# EEpromConfig.net
KiCad netlist of a schematic drawn in Altium Designer
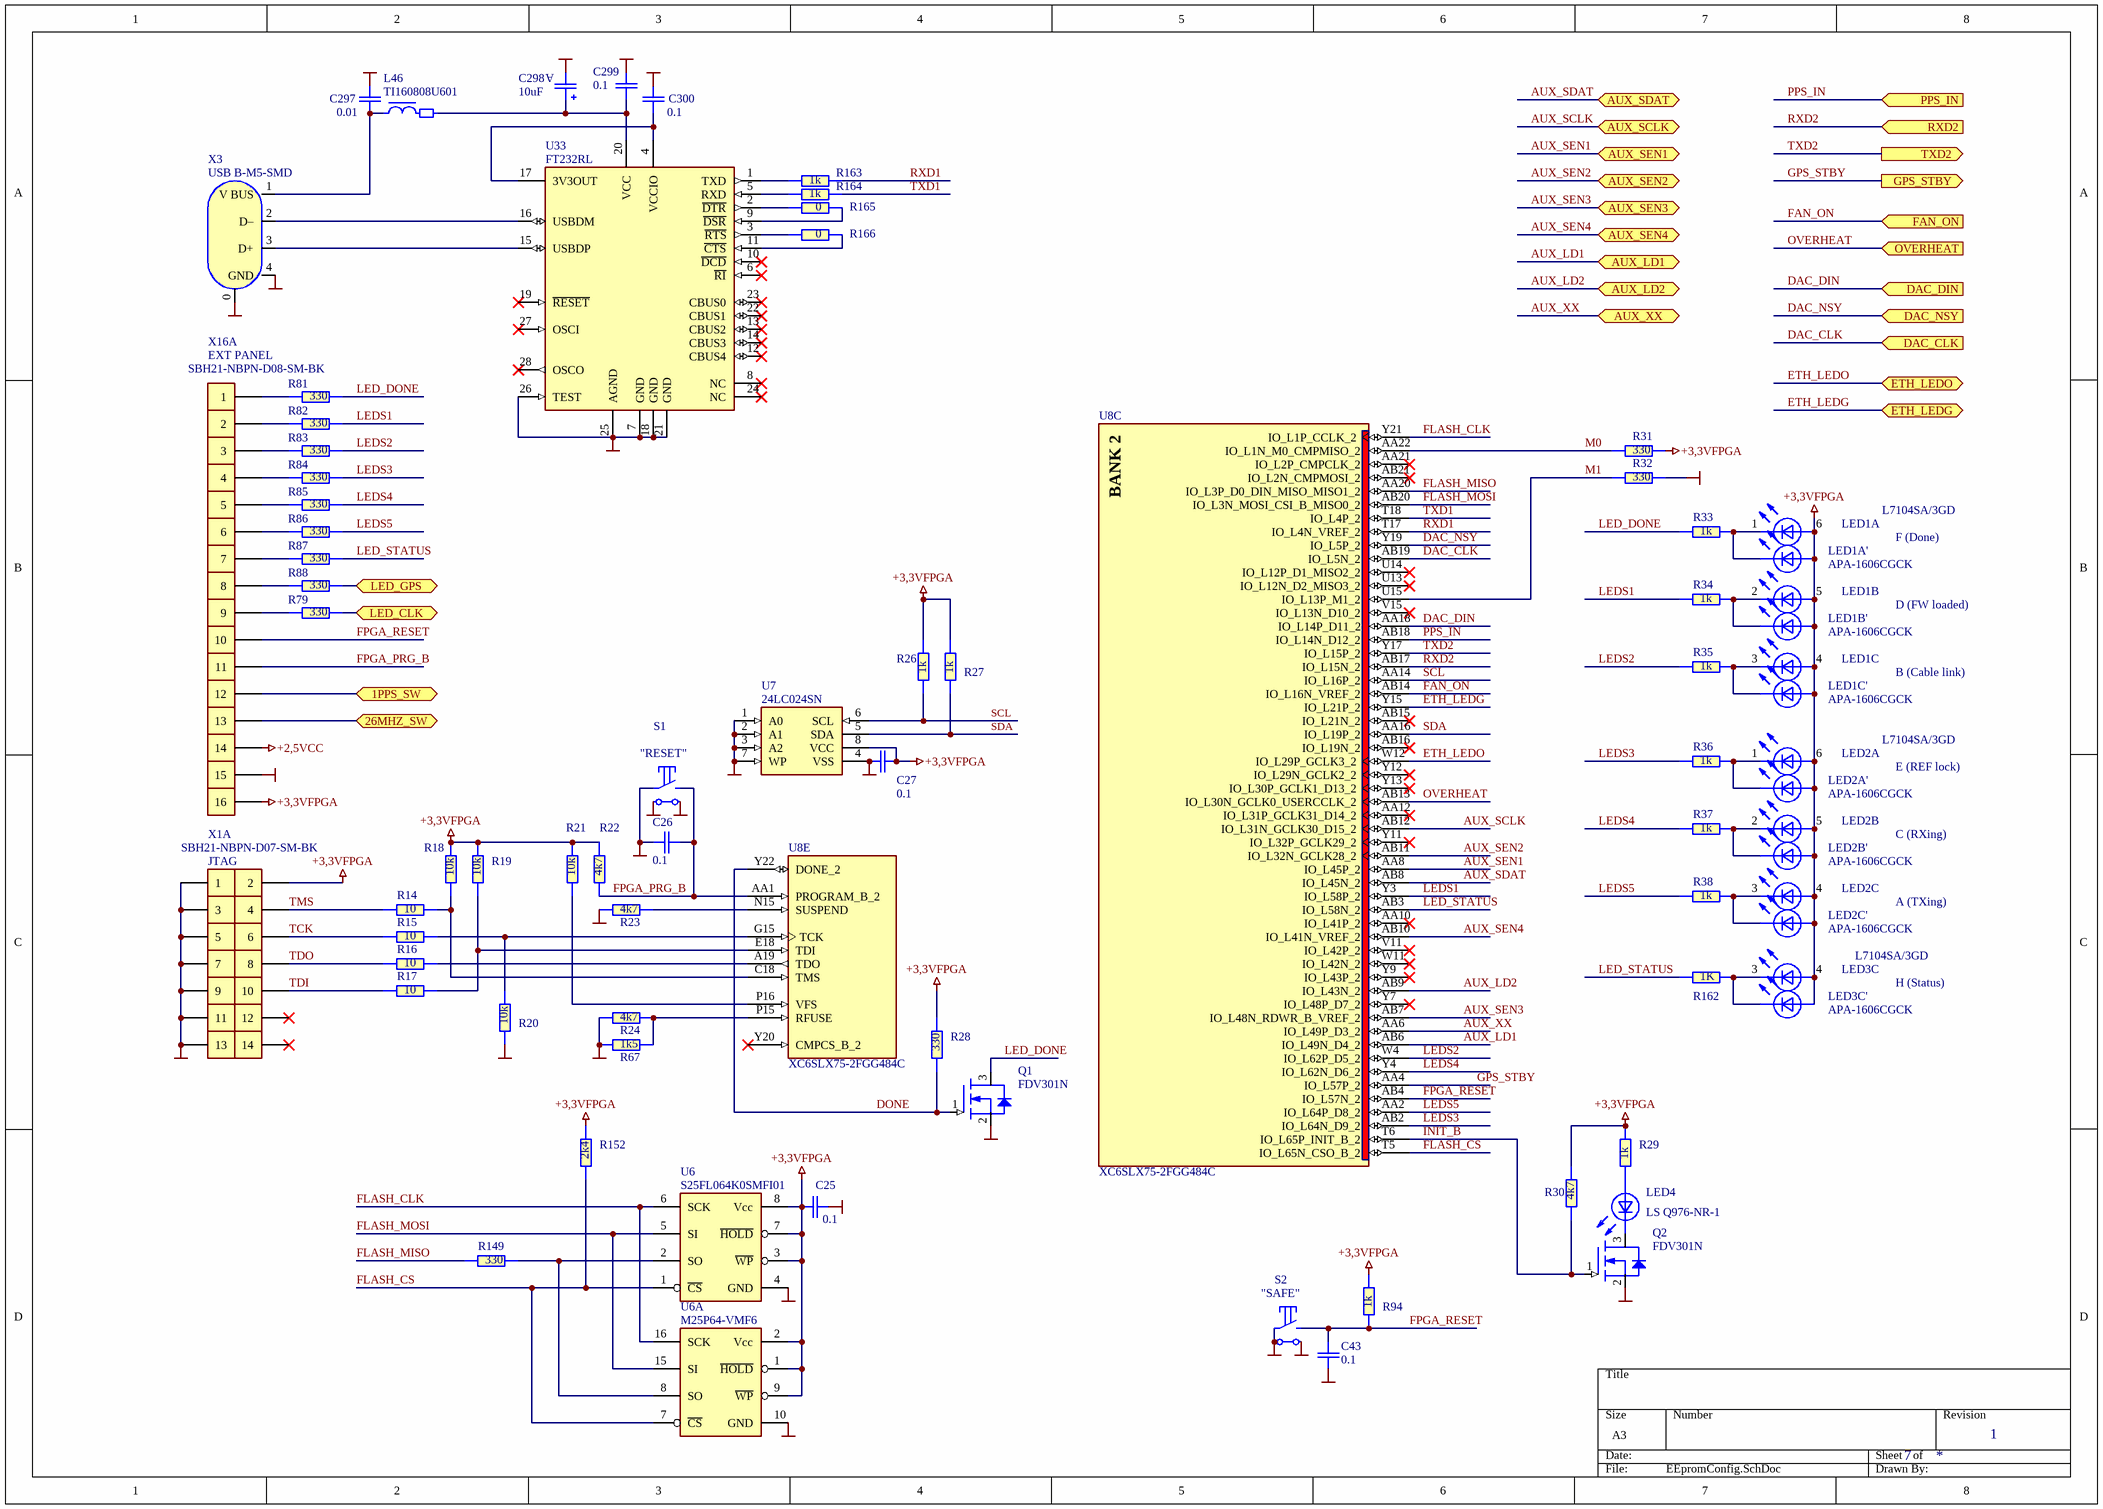
[diagram p0: EEpromConfig.SchDoc]

(export (version "E")
  (design (tool "Eeschema 10.0.6"))
  (components
    (comp (ref "C25")
      (value "0.1")
      (footprint "C0402-Phillips")
      (description "Конденсатор")
      (fields (field (name "MANUFACTURER") "MURATA") (field (name "TOLERANCE") "20%"))
      (libsource (lib "Capacitors") (part "C0402"))
    )
    (comp (ref "C26")
      (value "0.1")
      (footprint "C0402-Phillips")
      (description "Конденсатор")
      (fields (field (name "MANUFACTURER") "MURATA") (field (name "TOLERANCE") "20%"))
      (libsource (lib "Capacitors") (part "C0402"))
    )
    (comp (ref "C27")
      (value "0.1")
      (footprint "C0402-Phillips")
      (description "Конденсатор")
      (fields (field (name "MANUFACTURER") "MURATA") (field (name "TOLERANCE") "20%"))
      (libsource (lib "Capacitors") (part "C0402"))
    )
    (comp (ref "C43")
      (value "0.1")
      (footprint "C0402-Phillips")
      (description "Конденсатор")
      (fields (field (name "MANUFACTURER") "MURATA") (field (name "TOLERANCE") "20%"))
      (libsource (lib "Capacitors") (part "C0402"))
    )
    (comp (ref "C297")
      (value "0.01")
      (footprint "C0603-PHILLIPS")
      (description "Конденсатор")
      (fields (field (name "MANUFACTURER") "MURATA") (field (name "TOLERANCE") "20%"))
      (libsource (lib "Capacitors") (part "C0603"))
    )
    (comp (ref "C298")
      (value "10uF")
      (footprint "CA3216")
      (description "Конденсатор")
      (fields (field (name "MANUFACTURER") "SPRAGUE"))
      (libsource (lib "Capacitors") (part "CA3216"))
    )
    (comp (ref "C299")
      (value "0.1")
      (footprint "C0603-PHILLIPS")
      (description "Конденсатор")
      (fields (field (name "MANUFACTURER") "MURATA") (field (name "TOLERANCE") "20%"))
      (libsource (lib "Capacitors") (part "C0603"))
    )
    (comp (ref "C300")
      (value "0.1")
      (footprint "C0603-PHILLIPS")
      (description "Конденсатор")
      (fields (field (name "MANUFACTURER") "MURATA") (field (name "TOLERANCE") "20%"))
      (libsource (lib "Capacitors") (part "C0603"))
    )
    (comp (ref "L46")
      (value "TI160808U601")
      (footprint "Ti160808-Phillips")
      (description "Дроссель ЭМС")
      (fields (field (name "MANUFACTURER") "MURATA"))
      (libsource (lib "altium-import") (part "root_0_TI160808_"))
    )
    (comp (ref "LED1")
      (value "L7104SA/3GD")
      (footprint "L-7104SA/3")
      (description "Светодиод")
      (fields (field (name "MANUFACTURER") "KINGBRIGTH"))
      (libsource (lib "Diods") (part "L7104SA/3"))
    )
    (comp (ref "LED1A'")
      (value "APA-1606CGCK")
      (footprint "KPA-1606g")
      (description "Светодиод")
      (fields (field (name "MANUFACTURER") "Kingbright"))
      (libsource (lib "Diods") (part "KPA-1606"))
    )
    (comp (ref "LED1B'")
      (value "APA-1606CGCK")
      (footprint "KPA-1606g")
      (description "Светодиод")
      (fields (field (name "MANUFACTURER") "Kingbright"))
      (libsource (lib "Diods") (part "KPA-1606"))
    )
    (comp (ref "LED1C'")
      (value "APA-1606CGCK")
      (footprint "KPA-1606g")
      (description "Светодиод")
      (fields (field (name "MANUFACTURER") "Kingbright"))
      (libsource (lib "Diods") (part "KPA-1606"))
    )
    (comp (ref "LED2")
      (value "L7104SA/3GD")
      (footprint "L-7104SA/3")
      (description "Светодиод")
      (fields (field (name "MANUFACTURER") "KINGBRIGTH"))
      (libsource (lib "Diods") (part "L7104SA/3"))
    )
    (comp (ref "LED2A'")
      (value "APA-1606CGCK")
      (footprint "KPA-1606g")
      (description "Светодиод")
      (fields (field (name "MANUFACTURER") "Kingbright"))
      (libsource (lib "Diods") (part "KPA-1606"))
    )
    (comp (ref "LED2B'")
      (value "APA-1606CGCK")
      (footprint "KPA-1606g")
      (description "Светодиод")
      (fields (field (name "MANUFACTURER") "Kingbright"))
      (libsource (lib "Diods") (part "KPA-1606"))
    )
    (comp (ref "LED2C'")
      (value "APA-1606CGCK")
      (footprint "KPA-1606g")
      (description "Светодиод")
      (fields (field (name "MANUFACTURER") "Kingbright"))
      (libsource (lib "Diods") (part "KPA-1606"))
    )
    (comp (ref "LED3")
      (value "L7104SA/3GD")
      (footprint "L-7104SA/3")
      (description "Светодиод")
      (fields (field (name "MANUFACTURER") "KINGBRIGTH"))
      (libsource (lib "Diods") (part "L7104SA/3"))
    )
    (comp (ref "LED3C'")
      (value "APA-1606CGCK")
      (footprint "KPA-1606g")
      (description "Светодиод")
      (fields (field (name "MANUFACTURER") "Kingbright"))
      (libsource (lib "Diods") (part "KPA-1606"))
    )
    (comp (ref "LED4")
      (value "LS Q976-NR-1")
      (footprint "LED-0603y")
      (description "LED SMD")
      (fields (field (name "MANUFACTURER") "OSRAM Opto Semiconductors Inc"))
      (libsource (lib "altium-import") (part "root_2_LED0603_"))
    )
    (comp (ref "Q1")
      (value "FDV301N")
      (footprint "SOT23-Philips")
      (description "Транзистор")
      (fields (field (name "MANUFACTURER") "Fairchild"))
      (libsource (lib "Transistors") (part "FDV301N"))
    )
    (comp (ref "Q2")
      (value "FDV301N")
      (footprint "SOT23-Philips")
      (description "Транзистор")
      (fields (field (name "MANUFACTURER") "Fairchild"))
      (libsource (lib "Transistors") (part "FDV301N"))
    )
    (comp (ref "R14")
      (value "10")
      (footprint "R0603-PHILLIPS")
      (description "Резистор")
      (fields (field (name "MANUFACTURER") "YAGEO") (field (name "TOLERANCE") "5%"))
      (libsource (lib "altium-import") (part "root_1_R0603_"))
    )
    (comp (ref "R15")
      (value "10")
      (footprint "R0603-PHILLIPS")
      (description "Резистор")
      (fields (field (name "MANUFACTURER") "YAGEO") (field (name "TOLERANCE") "5%"))
      (libsource (lib "altium-import") (part "root_1_R0603_"))
    )
    (comp (ref "R16")
      (value "10")
      (footprint "R0603-PHILLIPS")
      (description "Резистор")
      (fields (field (name "MANUFACTURER") "YAGEO") (field (name "TOLERANCE") "5%"))
      (libsource (lib "altium-import") (part "root_1_R0603_"))
    )
    (comp (ref "R17")
      (value "10")
      (footprint "R0603-PHILLIPS")
      (description "Резистор")
      (fields (field (name "MANUFACTURER") "YAGEO") (field (name "TOLERANCE") "5%"))
      (libsource (lib "altium-import") (part "root_1_R0603_"))
    )
    (comp (ref "R18")
      (value "10k")
      (footprint "R0603-PHILLIPS")
      (description "Резистор")
      (fields (field (name "MANUFACTURER") "YAGEO") (field (name "TOLERANCE") "5%"))
      (libsource (lib "altium-import") (part "root_0_R0603_"))
    )
    (comp (ref "R19")
      (value "10k")
      (footprint "R0603-PHILLIPS")
      (description "Резистор")
      (fields (field (name "MANUFACTURER") "YAGEO") (field (name "TOLERANCE") "5%"))
      (libsource (lib "altium-import") (part "root_0_R0603_"))
    )
    (comp (ref "R20")
      (value "10k")
      (footprint "R0603-PHILLIPS")
      (description "Резистор")
      (fields (field (name "MANUFACTURER") "YAGEO") (field (name "TOLERANCE") "5%"))
      (libsource (lib "altium-import") (part "root_0_R0603_"))
    )
    (comp (ref "R21")
      (value "10k")
      (footprint "R0603-PHILLIPS")
      (description "Резистор")
      (fields (field (name "MANUFACTURER") "YAGEO") (field (name "TOLERANCE") "5%"))
      (libsource (lib "altium-import") (part "root_0_R0603_"))
    )
    (comp (ref "R22")
      (value "4k7")
      (footprint "R0603-PHILLIPS")
      (description "Резистор")
      (fields (field (name "MANUFACTURER") "YAGEO") (field (name "TOLERANCE") "5%"))
      (libsource (lib "altium-import") (part "root_0_R0603_"))
    )
    (comp (ref "R23")
      (value "4k7")
      (footprint "R0603-PHILLIPS")
      (description "Резистор")
      (fields (field (name "MANUFACTURER") "YAGEO") (field (name "TOLERANCE") "5%"))
      (libsource (lib "altium-import") (part "root_1_R0603_"))
    )
    (comp (ref "R24")
      (value "4k7")
      (footprint "R0603-PHILLIPS")
      (description "Резистор")
      (fields (field (name "MANUFACTURER") "YAGEO") (field (name "TOLERANCE") "5%"))
      (libsource (lib "altium-import") (part "root_1_R0603_"))
    )
    (comp (ref "R26")
      (value "1k")
      (footprint "R0603-PHILLIPS")
      (description "Резистор")
      (fields (field (name "MANUFACTURER") "YAGEO") (field (name "TOLERANCE") "5%"))
      (libsource (lib "altium-import") (part "root_0_R0603_"))
    )
    (comp (ref "R27")
      (value "1k")
      (footprint "R0603-PHILLIPS")
      (description "Резистор")
      (fields (field (name "MANUFACTURER") "YAGEO") (field (name "TOLERANCE") "5%"))
      (libsource (lib "altium-import") (part "root_0_R0603_"))
    )
    (comp (ref "R28")
      (value "330")
      (footprint "R0603-PHILLIPS")
      (description "Резистор")
      (fields (field (name "MANUFACTURER") "YAGEO") (field (name "TOLERANCE") "5%"))
      (libsource (lib "altium-import") (part "root_0_R0603_"))
    )
    (comp (ref "R29")
      (value "1k")
      (footprint "R0603-PHILLIPS")
      (description "Резистор")
      (fields (field (name "MANUFACTURER") "YAGEO") (field (name "TOLERANCE") "5%"))
      (libsource (lib "altium-import") (part "root_0_R0603_"))
    )
    (comp (ref "R30")
      (value "4k7")
      (footprint "R0603-PHILLIPS")
      (description "Резистор")
      (fields (field (name "MANUFACTURER") "YAGEO") (field (name "TOLERANCE") "5%"))
      (libsource (lib "altium-import") (part "root_0_R0603_"))
    )
    (comp (ref "R31")
      (value "330")
      (footprint "R0603-PHILLIPS")
      (description "Резистор")
      (fields (field (name "MANUFACTURER") "YAGEO") (field (name "TOLERANCE") "5%"))
      (libsource (lib "altium-import") (part "root_1_R0603_"))
    )
    (comp (ref "R32")
      (value "330")
      (footprint "R0603-PHILLIPS")
      (description "Резистор")
      (fields (field (name "MANUFACTURER") "YAGEO") (field (name "TOLERANCE") "5%"))
      (libsource (lib "altium-import") (part "root_1_R0603_"))
    )
    (comp (ref "R33")
      (value "1k")
      (footprint "R0603-PHILLIPS")
      (description "Резистор")
      (fields (field (name "MANUFACTURER") "YAGEO") (field (name "TOLERANCE") "5%"))
      (libsource (lib "altium-import") (part "root_3_R0603_"))
    )
    (comp (ref "R34")
      (value "1k")
      (footprint "R0603-PHILLIPS")
      (description "Резистор")
      (fields (field (name "MANUFACTURER") "YAGEO") (field (name "TOLERANCE") "5%"))
      (libsource (lib "altium-import") (part "root_3_R0603_"))
    )
    (comp (ref "R35")
      (value "1k")
      (footprint "R0603-PHILLIPS")
      (description "Резистор")
      (fields (field (name "MANUFACTURER") "YAGEO") (field (name "TOLERANCE") "5%"))
      (libsource (lib "altium-import") (part "root_3_R0603_"))
    )
    (comp (ref "R36")
      (value "1k")
      (footprint "R0603-PHILLIPS")
      (description "Резистор")
      (fields (field (name "MANUFACTURER") "YAGEO") (field (name "TOLERANCE") "5%"))
      (libsource (lib "altium-import") (part "root_3_R0603_"))
    )
    (comp (ref "R37")
      (value "1k")
      (footprint "R0603-PHILLIPS")
      (description "Резистор")
      (fields (field (name "MANUFACTURER") "YAGEO") (field (name "TOLERANCE") "5%"))
      (libsource (lib "altium-import") (part "root_3_R0603_"))
    )
    (comp (ref "R38")
      (value "1k")
      (footprint "R0603-PHILLIPS")
      (description "Резистор")
      (fields (field (name "MANUFACTURER") "YAGEO") (field (name "TOLERANCE") "5%"))
      (libsource (lib "altium-import") (part "root_3_R0603_"))
    )
    (comp (ref "R67")
      (value "1k5")
      (footprint "R0603-PHILLIPS")
      (description "Резистор")
      (fields (field (name "MANUFACTURER") "YAGEO") (field (name "TOLERANCE") "5%"))
      (libsource (lib "altium-import") (part "root_1_R0603_"))
    )
    (comp (ref "R79")
      (value "330")
      (footprint "R0603-PHILLIPS")
      (description "Резистор")
      (fields (field (name "MANUFACTURER") "YAGEO") (field (name "TOLERANCE") "5%"))
      (libsource (lib "altium-import") (part "root_3_mirrored_R0603_"))
    )
    (comp (ref "R81")
      (value "330")
      (footprint "R0603-PHILLIPS")
      (description "Резистор")
      (fields (field (name "MANUFACTURER") "YAGEO") (field (name "TOLERANCE") "5%"))
      (libsource (lib "altium-import") (part "root_3_mirrored_R0603_"))
    )
    (comp (ref "R82")
      (value "330")
      (footprint "R0603-PHILLIPS")
      (description "Резистор")
      (fields (field (name "MANUFACTURER") "YAGEO") (field (name "TOLERANCE") "5%"))
      (libsource (lib "altium-import") (part "root_3_mirrored_R0603_"))
    )
    (comp (ref "R83")
      (value "330")
      (footprint "R0603-PHILLIPS")
      (description "Резистор")
      (fields (field (name "MANUFACTURER") "YAGEO") (field (name "TOLERANCE") "5%"))
      (libsource (lib "altium-import") (part "root_3_mirrored_R0603_"))
    )
    (comp (ref "R84")
      (value "330")
      (footprint "R0603-PHILLIPS")
      (description "Резистор")
      (fields (field (name "MANUFACTURER") "YAGEO") (field (name "TOLERANCE") "5%"))
      (libsource (lib "altium-import") (part "root_3_mirrored_R0603_"))
    )
    (comp (ref "R85")
      (value "330")
      (footprint "R0603-PHILLIPS")
      (description "Резистор")
      (fields (field (name "MANUFACTURER") "YAGEO") (field (name "TOLERANCE") "5%"))
      (libsource (lib "altium-import") (part "root_3_mirrored_R0603_"))
    )
    (comp (ref "R86")
      (value "330")
      (footprint "R0603-PHILLIPS")
      (description "Резистор")
      (fields (field (name "MANUFACTURER") "YAGEO") (field (name "TOLERANCE") "5%"))
      (libsource (lib "altium-import") (part "root_3_mirrored_R0603_"))
    )
    (comp (ref "R87")
      (value "330")
      (footprint "R0603-PHILLIPS")
      (description "Резистор")
      (fields (field (name "MANUFACTURER") "YAGEO") (field (name "TOLERANCE") "5%"))
      (libsource (lib "altium-import") (part "root_3_mirrored_R0603_"))
    )
    (comp (ref "R88")
      (value "330")
      (footprint "R0603-PHILLIPS")
      (description "Резистор")
      (fields (field (name "MANUFACTURER") "YAGEO") (field (name "TOLERANCE") "5%"))
      (libsource (lib "altium-import") (part "root_3_mirrored_R0603_"))
    )
    (comp (ref "R94")
      (value "1k")
      (footprint "R0603-PHILLIPS")
      (description "Резистор")
      (fields (field (name "MANUFACTURER") "YAGEO") (field (name "TOLERANCE") "5%"))
      (libsource (lib "altium-import") (part "root_0_R0603_"))
    )
    (comp (ref "R149")
      (value "330")
      (footprint "R0603-PHILLIPS")
      (description "Резистор")
      (fields (field (name "MANUFACTURER") "YAGEO") (field (name "TOLERANCE") "5%"))
      (libsource (lib "altium-import") (part "root_1_R0603_"))
    )
    (comp (ref "R152")
      (value "2k4")
      (footprint "R0603-PHILLIPS")
      (description "Резистор")
      (fields (field (name "MANUFACTURER") "YAGEO") (field (name "TOLERANCE") "5%"))
      (libsource (lib "altium-import") (part "root_0_R0603_"))
    )
    (comp (ref "R162")
      (value "1K")
      (footprint "R0603-PHILLIPS")
      (description "Резистор")
      (fields (field (name "MANUFACTURER") "YAGEO") (field (name "TOLERANCE") "5%"))
      (libsource (lib "altium-import") (part "root_1_R0603_"))
    )
    (comp (ref "R163")
      (value "1k")
      (footprint "R0603-PHILLIPS")
      (description "Резистор")
      (fields (field (name "MANUFACTURER") "YAGEO") (field (name "TOLERANCE") "5%"))
      (libsource (lib "altium-import") (part "root_3_R0603_"))
    )
    (comp (ref "R164")
      (value "1k")
      (footprint "R0603-PHILLIPS")
      (description "Резистор")
      (fields (field (name "MANUFACTURER") "YAGEO") (field (name "TOLERANCE") "5%"))
      (libsource (lib "altium-import") (part "root_3_R0603_"))
    )
    (comp (ref "R165")
      (value "0")
      (footprint "R0603-PHILLIPS")
      (description "Резистор")
      (fields (field (name "MANUFACTURER") "YAGEO") (field (name "TOLERANCE") "5%"))
      (libsource (lib "Resistors") (part "R0603"))
    )
    (comp (ref "R166")
      (value "0")
      (footprint "R0603-PHILLIPS")
      (description "Резистор")
      (fields (field (name "MANUFACTURER") "YAGEO") (field (name "TOLERANCE") "5%"))
      (libsource (lib "Resistors") (part "R0603"))
    )
    (comp (ref "S1")
      (value "TL3340AF160QG")
      (footprint "TL3340")
      (description "Switch Tactile SMD right angle")
      (fields (field (name "MANUFACTURER") "E-Switch") (field (name "MISC") "\"RESET\""))
      (libsource (lib "Andy") (part "TL3340AF160QG"))
    )
    (comp (ref "S2")
      (value "TL3340AF160QG")
      (footprint "TL3340")
      (description "Switch Tactile SMD right angle")
      (fields (field (name "MANUFACTURER") "E-Switch") (field (name "MISC") "\"SAFE\""))
      (libsource (lib "Andy") (part "TL3340AF160QG"))
    )
    (comp (ref "U6")
      (value "S25FL064K0SMFI01")
      (footprint "SO-8[wide200]")
      (description "Микросхема")
      (fields (field (name "MANUFACTURER") "SPANSION"))
      (libsource (lib "Andy") (part "S25FL064K"))
    )
    (comp (ref "U6A")
      (value "M25P64-VMF6")
      (footprint "so-16W")
      (description "Микросхема")
      (fields (field (name "MANUFACTURER") "ST"))
      (libsource (lib "Andy") (part "M25P64-VMF6"))
    )
    (comp (ref "U7")
      (value "24LC024SN")
      (footprint "SOIC8")
      (description "Микросхема")
      (fields (field (name "MANUFACTURER") "Microchip"))
      (libsource (lib "altium-import") (part "root_0_AT24CXX_"))
    )
    (comp (ref "U8")
      (value "XC6SLX75-2FGG484C")
      (footprint "FBGA484")
      (fields (field (name "MANUFACTURER") "Xilinx"))
      (libsource (lib "MicroCircuitsM-Z") (part "XC6SLX75-2FGG484C"))
    )
    (comp (ref "U33")
      (value "FT232RL")
      (footprint "SSOP-28(5.3X10/0.65)")
      (description "Микросхема")
      (fields (field (name "MANUFACTURER") "FTDI"))
      (libsource (lib "Andy") (part "FT232RL"))
    )
    (comp (ref "X1")
      (value "SBH21-NBPN-D07-SM-BK")
      (footprint "SBH-14")
      (description "Разъем")
      (fields (field (name "MANUFACTURER") "Sullins") (field (name "OTHER") "JTAG"))
      (libsource (lib "") (part "SBH21-7x2_SMD_3"))
    )
    (comp (ref "X3")
      (value "USB B-M5-SMD")
      (footprint "USB/SM0.8-6H5")
      (description "Разъём")
      (libsource (lib "Connectors") (part "USB M-1J"))
    )
    (comp (ref "X16")
      (value "SBH21-NBPN-D08-SM-BK")
      (footprint "SBH-16")
      (description "Connector 2mm SMD")
      (fields (field (name "MANUFACTURER") "Sullins") (field (name "MISC") "EXT PANEL"))
      (libsource (lib "Andy") (part "SBH21-8x2_SMD"))
    )
  )
  (nets
    (net (code "1") (name "+2,5VCC") (class "Default")
      (node (ref "X16") (pin "14") (pinfunction "14_14") (pintype "passive"))
    )
    (net (code "2") (name "+3,3VFPGA") (class "Default")
      (node (ref "C25") (pin "1") (pinfunction "1_1") (pintype "passive"))
      (node (ref "C27") (pin "2") (pinfunction "2_2") (pintype "passive"))
      (node (ref "LED1") (pin "4") (pinfunction "A3_4") (pintype "passive"))
      (node (ref "LED1") (pin "5") (pinfunction "A2_5") (pintype "passive"))
      (node (ref "LED1") (pin "6") (pinfunction "A1_6") (pintype "passive"))
      (node (ref "LED1A'") (pin "2") (pinfunction "A_2") (pintype "passive"))
      (node (ref "LED1B'") (pin "2") (pinfunction "A_2") (pintype "passive"))
      (node (ref "LED1C'") (pin "2") (pinfunction "A_2") (pintype "passive"))
      (node (ref "LED2") (pin "4") (pinfunction "A3_4") (pintype "passive"))
      (node (ref "LED2") (pin "5") (pinfunction "A2_5") (pintype "passive"))
      (node (ref "LED2") (pin "6") (pinfunction "A1_6") (pintype "passive"))
      (node (ref "LED2A'") (pin "2") (pinfunction "A_2") (pintype "passive"))
      (node (ref "LED2B'") (pin "2") (pinfunction "A_2") (pintype "passive"))
      (node (ref "LED2C'") (pin "2") (pinfunction "A_2") (pintype "passive"))
      (node (ref "LED3") (pin "4") (pinfunction "A3_4") (pintype "passive"))
      (node (ref "LED3C'") (pin "2") (pinfunction "A_2") (pintype "passive"))
      (node (ref "R152") (pin "1") (pinfunction "1_1") (pintype "passive"))
      (node (ref "R18") (pin "1") (pinfunction "1_1") (pintype "passive"))
      (node (ref "R19") (pin "1") (pinfunction "1_1") (pintype "passive"))
      (node (ref "R21") (pin "1") (pinfunction "1_1") (pintype "passive"))
      (node (ref "R22") (pin "1") (pinfunction "1_1") (pintype "passive"))
      (node (ref "R26") (pin "1") (pinfunction "1_1") (pintype "passive"))
      (node (ref "R27") (pin "1") (pinfunction "1_1") (pintype "passive"))
      (node (ref "R28") (pin "1") (pinfunction "1_1") (pintype "passive"))
      (node (ref "R29") (pin "1") (pinfunction "1_1") (pintype "passive"))
      (node (ref "R30") (pin "1") (pinfunction "1_1") (pintype "passive"))
      (node (ref "R31") (pin "2") (pinfunction "2_2") (pintype "passive"))
      (node (ref "R94") (pin "1") (pinfunction "1_1") (pintype "passive"))
      (node (ref "U6") (pin "3") (pinfunction "~{WP}_3") (pintype "passive"))
      (node (ref "U6") (pin "7") (pinfunction "~{HOLD}_7") (pintype "passive"))
      (node (ref "U6") (pin "8") (pinfunction "Vcc_8") (pintype "passive"))
      (node (ref "U6A") (pin "1") (pinfunction "~{HOLD}_1") (pintype "passive"))
      (node (ref "U6A") (pin "2") (pinfunction "Vcc_2") (pintype "passive"))
      (node (ref "U6A") (pin "9") (pinfunction "~{WP}_9") (pintype "passive"))
      (node (ref "U7") (pin "8") (pinfunction "VCC_8") (pintype "power_in"))
      (node (ref "X1") (pin "2") (pinfunction "2_2") (pintype "passive"))
      (node (ref "X16") (pin "16") (pinfunction "16_16") (pintype "passive"))
    )
    (net (code "3") (name "/1PPS_SW") (class "Default")
      (node (ref "X16") (pin "12") (pinfunction "12_12") (pintype "passive"))
    )
    (net (code "4") (name "/26MHZ_SW") (class "Default")
      (node (ref "X16") (pin "13") (pinfunction "13_13") (pintype "passive"))
    )
    (net (code "5") (name "/AUX_LD1") (class "Default")
      (node (ref "U8") (pin "AB6") (pinfunction "IO_L49N_D4_2_AB6") (pintype "bidirectional"))
    )
    (net (code "6") (name "/AUX_LD2") (class "Default")
      (node (ref "U8") (pin "AB9") (pinfunction "IO_L43N_2_AB9") (pintype "bidirectional"))
    )
    (net (code "7") (name "/AUX_SCLK") (class "Default")
      (node (ref "U8") (pin "AB12") (pinfunction "IO_L31N_GCLK30_D15_2_AB12") (pintype "bidirectional"))
    )
    (net (code "8") (name "/AUX_SDAT") (class "Default")
      (node (ref "U8") (pin "AB8") (pinfunction "IO_L45N_2_AB8") (pintype "bidirectional"))
    )
    (net (code "9") (name "/AUX_SEN1") (class "Default")
      (node (ref "U8") (pin "AA8") (pinfunction "IO_L45P_2_AA8") (pintype "bidirectional"))
    )
    (net (code "10") (name "/AUX_SEN2") (class "Default")
      (node (ref "U8") (pin "AB11") (pinfunction "IO_L32N_GCLK28_2_AB11") (pintype "bidirectional"))
    )
    (net (code "11") (name "/AUX_SEN3") (class "Default")
      (node (ref "U8") (pin "AB7") (pinfunction "IO_L48N_RDWR_B_VREF_2_AB7") (pintype "bidirectional"))
    )
    (net (code "12") (name "/AUX_SEN4") (class "Default")
      (node (ref "U8") (pin "AB10") (pinfunction "IO_L41N_VREF_2_AB10") (pintype "bidirectional"))
    )
    (net (code "13") (name "/AUX_XX") (class "Default")
      (node (ref "U8") (pin "AA6") (pinfunction "IO_L49P_D3_2_AA6") (pintype "bidirectional"))
    )
    (net (code "14") (name "/DAC_CLK") (class "Default")
      (node (ref "U8") (pin "AB19") (pinfunction "IO_L5N_2_AB19") (pintype "bidirectional"))
    )
    (net (code "15") (name "/DAC_DIN") (class "Default")
      (node (ref "U8") (pin "AA18") (pinfunction "IO_L14P_D11_2_AA18") (pintype "bidirectional"))
    )
    (net (code "16") (name "/DAC_NSY") (class "Default")
      (node (ref "U8") (pin "Y19") (pinfunction "IO_L5P_2_Y19") (pintype "bidirectional"))
    )
    (net (code "17") (name "/DONE") (class "Default")
      (node (ref "Q1") (pin "1") (pinfunction "G_1") (pintype "input"))
      (node (ref "R28") (pin "2") (pinfunction "2_2") (pintype "passive"))
      (node (ref "U8") (pin "Y22") (pinfunction "DONE_2_Y22") (pintype "bidirectional"))
    )
    (net (code "18") (name "/ETH_LEDG") (class "Default")
      (node (ref "U8") (pin "Y15") (pinfunction "IO_L21P_2_Y15") (pintype "bidirectional"))
    )
    (net (code "19") (name "/ETH_LEDO") (class "Default")
      (node (ref "U8") (pin "W12") (pinfunction "IO_L29P_GCLK3_2_W12") (pintype "bidirectional"))
    )
    (net (code "20") (name "/FAN_ON") (class "Default")
      (node (ref "U8") (pin "AB14") (pinfunction "IO_L16N_VREF_2_AB14") (pintype "bidirectional"))
    )
    (net (code "21") (name "/FLASH_CLK") (class "Default")
      (node (ref "U6") (pin "6") (pinfunction "SCK_6") (pintype "passive"))
      (node (ref "U6A") (pin "16") (pinfunction "SCK_16") (pintype "passive"))
      (node (ref "U8") (pin "Y21") (pinfunction "IO_L1P_CCLK_2_Y21") (pintype "bidirectional"))
    )
    (net (code "22") (name "/FLASH_CS") (class "Default")
      (node (ref "R152") (pin "2") (pinfunction "2_2") (pintype "passive"))
      (node (ref "U6") (pin "1") (pinfunction "~{CS}_1") (pintype "passive"))
      (node (ref "U6A") (pin "7") (pinfunction "~{CS}_7") (pintype "passive"))
      (node (ref "U8") (pin "T5") (pinfunction "IO_L65N_CSO_B_2_T5") (pintype "bidirectional"))
    )
    (net (code "23") (name "/FLASH_MISO") (class "Default")
      (node (ref "R149") (pin "1") (pinfunction "1_1") (pintype "passive"))
      (node (ref "U8") (pin "AA20") (pinfunction "IO_L3P_D0_DIN_MISO_MISO1_2_AA20") (pintype "bidirectional"))
    )
    (net (code "24") (name "/FLASH_MOSI") (class "Default")
      (node (ref "U6") (pin "5") (pinfunction "SI_5") (pintype "passive"))
      (node (ref "U6A") (pin "15") (pinfunction "SI_15") (pintype "passive"))
      (node (ref "U8") (pin "AB20") (pinfunction "IO_L3N_MOSI_CSI_B_MISO0_2_AB20") (pintype "bidirectional"))
    )
    (net (code "25") (name "/FPGA_PRG_B") (class "Default")
      (node (ref "C26") (pin "1") (pinfunction "1_1") (pintype "passive"))
      (node (ref "R22") (pin "2") (pinfunction "2_2") (pintype "passive"))
      (node (ref "S1") (pin "1") (pinfunction "1_1") (pintype "passive"))
      (node (ref "U8") (pin "AA1") (pinfunction "PROGRAM_B_2_AA1") (pintype "input"))
      (node (ref "X16") (pin "11") (pinfunction "11_11") (pintype "passive"))
    )
    (net (code "26") (name "/FPGA_RESET") (class "Default")
      (node (ref "C43") (pin "2") (pinfunction "2_2") (pintype "passive"))
      (node (ref "R94") (pin "2") (pinfunction "2_2") (pintype "passive"))
      (node (ref "S2") (pin "1") (pinfunction "1_1") (pintype "passive"))
      (node (ref "U8") (pin "AB4") (pinfunction "IO_L57N_2_AB4") (pintype "bidirectional"))
      (node (ref "X16") (pin "10") (pinfunction "10_10") (pintype "passive"))
    )
    (net (code "27") (name "/GPS_STBY") (class "Default")
      (node (ref "U8") (pin "AA4") (pinfunction "IO_L57P_2_AA4") (pintype "bidirectional"))
    )
    (net (code "28") (name "/INIT_B") (class "Default")
      (node (ref "Q2") (pin "1") (pinfunction "G_1") (pintype "input"))
      (node (ref "R30") (pin "2") (pinfunction "2_2") (pintype "passive"))
      (node (ref "U8") (pin "T6") (pinfunction "IO_L65P_INIT_B_2_T6") (pintype "bidirectional"))
    )
    (net (code "29") (name "/LEDS1") (class "Default")
      (node (ref "R34") (pin "2") (pinfunction "2_2") (pintype "passive"))
      (node (ref "R82") (pin "2") (pinfunction "2_2") (pintype "passive"))
      (node (ref "U8") (pin "Y3") (pinfunction "IO_L58P_2_Y3") (pintype "bidirectional"))
    )
    (net (code "30") (name "/LEDS2") (class "Default")
      (node (ref "R35") (pin "2") (pinfunction "2_2") (pintype "passive"))
      (node (ref "R83") (pin "2") (pinfunction "2_2") (pintype "passive"))
      (node (ref "U8") (pin "W4") (pinfunction "IO_L62P_D5_2_W4") (pintype "bidirectional"))
    )
    (net (code "31") (name "/LEDS3") (class "Default")
      (node (ref "R36") (pin "2") (pinfunction "2_2") (pintype "passive"))
      (node (ref "R84") (pin "2") (pinfunction "2_2") (pintype "passive"))
      (node (ref "U8") (pin "AB2") (pinfunction "IO_L64N_D9_2_AB2") (pintype "bidirectional"))
    )
    (net (code "32") (name "/LEDS4") (class "Default")
      (node (ref "R37") (pin "2") (pinfunction "2_2") (pintype "passive"))
      (node (ref "R85") (pin "2") (pinfunction "2_2") (pintype "passive"))
      (node (ref "U8") (pin "Y4") (pinfunction "IO_L62N_D6_2_Y4") (pintype "bidirectional"))
    )
    (net (code "33") (name "/LEDS5") (class "Default")
      (node (ref "R38") (pin "2") (pinfunction "2_2") (pintype "passive"))
      (node (ref "R86") (pin "2") (pinfunction "2_2") (pintype "passive"))
      (node (ref "U8") (pin "AA2") (pinfunction "IO_L64P_D8_2_AA2") (pintype "bidirectional"))
    )
    (net (code "34") (name "/LED_CLK") (class "Default")
      (node (ref "R79") (pin "2") (pinfunction "2_2") (pintype "passive"))
    )
    (net (code "35") (name "/LED_DONE") (class "Default")
      (node (ref "Q1") (pin "3") (pinfunction "D_3") (pintype "passive"))
      (node (ref "R33") (pin "2") (pinfunction "2_2") (pintype "passive"))
      (node (ref "R81") (pin "2") (pinfunction "2_2") (pintype "passive"))
    )
    (net (code "36") (name "/LED_GPS") (class "Default")
      (node (ref "R88") (pin "2") (pinfunction "2_2") (pintype "passive"))
    )
    (net (code "37") (name "/LED_STATUS") (class "Default")
      (node (ref "R162") (pin "1") (pinfunction "1_1") (pintype "passive"))
      (node (ref "R87") (pin "2") (pinfunction "2_2") (pintype "passive"))
      (node (ref "U8") (pin "AB3") (pinfunction "IO_L58N_2_AB3") (pintype "bidirectional"))
    )
    (net (code "38") (name "/M0") (class "Default")
      (node (ref "R31") (pin "1") (pinfunction "1_1") (pintype "passive"))
      (node (ref "U8") (pin "AA22") (pinfunction "IO_L1N_M0_CMPMISO_2_AA22") (pintype "bidirectional"))
    )
    (net (code "39") (name "/M1") (class "Default")
      (node (ref "R32") (pin "1") (pinfunction "1_1") (pintype "passive"))
      (node (ref "U8") (pin "U15") (pinfunction "IO_L13P_M1_2_U15") (pintype "bidirectional"))
    )
    (net (code "40") (name "/OVERHEAT") (class "Default")
      (node (ref "U8") (pin "AB13") (pinfunction "IO_L30N_GCLK0_USERCCLK_2_AB13") (pintype "bidirectional"))
    )
    (net (code "41") (name "/PPS_IN") (class "Default")
      (node (ref "U8") (pin "AB18") (pinfunction "IO_L14N_D12_2_AB18") (pintype "bidirectional"))
    )
    (net (code "42") (name "/RXD1") (class "Default")
      (node (ref "R163") (pin "1") (pinfunction "1_1") (pintype "passive"))
      (node (ref "U8") (pin "T17") (pinfunction "IO_L4N_VREF_2_T17") (pintype "bidirectional"))
    )
    (net (code "43") (name "/RXD2") (class "Default")
      (node (ref "U8") (pin "AB17") (pinfunction "IO_L15N_2_AB17") (pintype "bidirectional"))
    )
    (net (code "44") (name "/SCL") (class "Default")
      (node (ref "R26") (pin "2") (pinfunction "2_2") (pintype "passive"))
      (node (ref "U7") (pin "6") (pinfunction "SCL_6") (pintype "input"))
      (node (ref "U8") (pin "AA14") (pinfunction "IO_L16P_2_AA14") (pintype "bidirectional"))
    )
    (net (code "45") (name "/SDA") (class "Default")
      (node (ref "R27") (pin "2") (pinfunction "2_2") (pintype "passive"))
      (node (ref "U7") (pin "5") (pinfunction "SDA_5") (pintype "passive"))
      (node (ref "U8") (pin "AA16") (pinfunction "IO_L19P_2_AA16") (pintype "bidirectional"))
    )
    (net (code "46") (name "/TCK") (class "Default")
      (node (ref "R15") (pin "1") (pinfunction "1_1") (pintype "passive"))
      (node (ref "X1") (pin "6") (pinfunction "6_6") (pintype "passive"))
    )
    (net (code "47") (name "/TDI") (class "Default")
      (node (ref "R17") (pin "1") (pinfunction "1_1") (pintype "passive"))
      (node (ref "X1") (pin "10") (pinfunction "10_10") (pintype "passive"))
    )
    (net (code "48") (name "/TDO") (class "Default")
      (node (ref "R16") (pin "1") (pinfunction "1_1") (pintype "passive"))
      (node (ref "X1") (pin "8") (pinfunction "8_8") (pintype "passive"))
    )
    (net (code "49") (name "/TMS") (class "Default")
      (node (ref "R14") (pin "1") (pinfunction "1_1") (pintype "passive"))
      (node (ref "X1") (pin "4") (pinfunction "4_4") (pintype "passive"))
    )
    (net (code "50") (name "/TXD1") (class "Default")
      (node (ref "R164") (pin "1") (pinfunction "1_1") (pintype "passive"))
      (node (ref "U8") (pin "T18") (pinfunction "IO_L4P_2_T18") (pintype "bidirectional"))
    )
    (net (code "51") (name "/TXD2") (class "Default")
      (node (ref "U8") (pin "Y17") (pinfunction "IO_L15P_2_Y17") (pintype "bidirectional"))
    )
    (net (code "52") (name "GND") (class "Default")
      (node (ref "C25") (pin "2") (pinfunction "2_2") (pintype "passive"))
      (node (ref "C26") (pin "2") (pinfunction "2_2") (pintype "passive"))
      (node (ref "C27") (pin "1") (pinfunction "1_1") (pintype "passive"))
      (node (ref "C297") (pin "1") (pinfunction "1_1") (pintype "passive"))
      (node (ref "C298") (pin "2") (pinfunction "-_2") (pintype "passive"))
      (node (ref "C299") (pin "1") (pinfunction "1_1") (pintype "passive"))
      (node (ref "C300") (pin "1") (pinfunction "1_1") (pintype "passive"))
      (node (ref "C43") (pin "1") (pinfunction "1_1") (pintype "passive"))
      (node (ref "Q1") (pin "2") (pinfunction "S_2") (pintype "passive"))
      (node (ref "Q2") (pin "2") (pinfunction "S_2") (pintype "passive"))
      (node (ref "R20") (pin "2") (pinfunction "2_2") (pintype "passive"))
      (node (ref "R23") (pin "1") (pinfunction "1_1") (pintype "passive"))
      (node (ref "R24") (pin "1") (pinfunction "1_1") (pintype "passive"))
      (node (ref "R32") (pin "2") (pinfunction "2_2") (pintype "passive"))
      (node (ref "R67") (pin "1") (pinfunction "1_1") (pintype "passive"))
      (node (ref "S1") (pin "2") (pinfunction "2_2") (pintype "passive"))
      (node (ref "S1") (pin "3") (pinfunction "3_3") (pintype "passive"))
      (node (ref "S1") (pin "4") (pinfunction "4_4") (pintype "passive"))
      (node (ref "S2") (pin "2") (pinfunction "2_2") (pintype "passive"))
      (node (ref "S2") (pin "3") (pinfunction "3_3") (pintype "passive"))
      (node (ref "S2") (pin "4") (pinfunction "4_4") (pintype "passive"))
      (node (ref "U33") (pin "18") (pinfunction "GND_18") (pintype "power_in"))
      (node (ref "U33") (pin "21") (pinfunction "GND_21") (pintype "power_in"))
      (node (ref "U33") (pin "25") (pinfunction "AGND_25") (pintype "power_in"))
      (node (ref "U33") (pin "26") (pinfunction "TEST_26") (pintype "input"))
      (node (ref "U33") (pin "7") (pinfunction "GND_7") (pintype "power_in"))
      (node (ref "U6") (pin "4") (pinfunction "GND_4") (pintype "passive"))
      (node (ref "U6A") (pin "10") (pinfunction "GND_10") (pintype "passive"))
      (node (ref "U7") (pin "1") (pinfunction "A0_1") (pintype "input"))
      (node (ref "U7") (pin "2") (pinfunction "A1_2") (pintype "input"))
      (node (ref "U7") (pin "3") (pinfunction "A2_3") (pintype "input"))
      (node (ref "U7") (pin "4") (pinfunction "VSS_4") (pintype "power_in"))
      (node (ref "U7") (pin "7") (pinfunction "WP_7") (pintype "input"))
      (node (ref "X1") (pin "1") (pinfunction "1_1") (pintype "passive"))
      (node (ref "X1") (pin "11") (pinfunction "11_11") (pintype "passive"))
      (node (ref "X1") (pin "13") (pinfunction "13_13") (pintype "passive"))
      (node (ref "X1") (pin "3") (pinfunction "3_3") (pintype "passive"))
      (node (ref "X1") (pin "5") (pinfunction "5_5") (pintype "passive"))
      (node (ref "X1") (pin "7") (pinfunction "7_7") (pintype "passive"))
      (node (ref "X1") (pin "9") (pinfunction "9_9") (pintype "passive"))
      (node (ref "X16") (pin "15") (pinfunction "15_15") (pintype "passive"))
      (node (ref "X3") (pin "0") (pinfunction "GND_0") (pintype "power_in"))
      (node (ref "X3") (pin "4") (pinfunction "GND_4") (pintype "power_in"))
    )
    (net (code "53") (name "Net-(C298-+)") (class "Default")
      (node (ref "C298") (pin "1") (pinfunction "+_1") (pintype "passive"))
      (node (ref "C299") (pin "2") (pinfunction "2_2") (pintype "passive"))
      (node (ref "L46") (pin "2") (pinfunction "2_2") (pintype "passive"))
      (node (ref "U33") (pin "20") (pinfunction "VCC_20") (pintype "power_in"))
    )
    (net (code "54") (name "Net-(LED1A'-K)") (class "Default")
      (node (ref "LED1") (pin "1") (pinfunction "K1_1") (pintype "passive"))
      (node (ref "LED1A'") (pin "1") (pinfunction "K_1") (pintype "passive"))
      (node (ref "R33") (pin "1") (pinfunction "1_1") (pintype "passive"))
    )
    (net (code "55") (name "Net-(LED1B'-K)") (class "Default")
      (node (ref "LED1") (pin "2") (pinfunction "K2_2") (pintype "passive"))
      (node (ref "LED1B'") (pin "1") (pinfunction "K_1") (pintype "passive"))
      (node (ref "R34") (pin "1") (pinfunction "1_1") (pintype "passive"))
    )
    (net (code "56") (name "Net-(LED1C'-K)") (class "Default")
      (node (ref "LED1") (pin "3") (pinfunction "K3_3") (pintype "passive"))
      (node (ref "LED1C'") (pin "1") (pinfunction "K_1") (pintype "passive"))
      (node (ref "R35") (pin "1") (pinfunction "1_1") (pintype "passive"))
    )
    (net (code "57") (name "Net-(LED2A'-K)") (class "Default")
      (node (ref "LED2") (pin "1") (pinfunction "K1_1") (pintype "passive"))
      (node (ref "LED2A'") (pin "1") (pinfunction "K_1") (pintype "passive"))
      (node (ref "R36") (pin "1") (pinfunction "1_1") (pintype "passive"))
    )
    (net (code "58") (name "Net-(LED2B'-K)") (class "Default")
      (node (ref "LED2") (pin "2") (pinfunction "K2_2") (pintype "passive"))
      (node (ref "LED2B'") (pin "1") (pinfunction "K_1") (pintype "passive"))
      (node (ref "R37") (pin "1") (pinfunction "1_1") (pintype "passive"))
    )
    (net (code "59") (name "Net-(LED2C'-K)") (class "Default")
      (node (ref "LED2") (pin "3") (pinfunction "K3_3") (pintype "passive"))
      (node (ref "LED2C'") (pin "1") (pinfunction "K_1") (pintype "passive"))
      (node (ref "R38") (pin "1") (pinfunction "1_1") (pintype "passive"))
    )
    (net (code "60") (name "Net-(LED3C'-K)") (class "Default")
      (node (ref "LED3") (pin "3") (pinfunction "K3_3") (pintype "passive"))
      (node (ref "LED3C'") (pin "1") (pinfunction "K_1") (pintype "passive"))
      (node (ref "R162") (pin "2") (pinfunction "2_2") (pintype "passive"))
    )
    (net (code "61") (name "Net-(LED4-A)") (class "Default")
      (node (ref "LED4") (pin "2") (pinfunction "A_2") (pintype "passive"))
      (node (ref "R29") (pin "2") (pinfunction "2_2") (pintype "passive"))
    )
    (net (code "62") (name "Net-(LED4-K)") (class "Default")
      (node (ref "LED4") (pin "1") (pinfunction "K_1") (pintype "passive"))
      (node (ref "Q2") (pin "3") (pinfunction "D_3") (pintype "passive"))
    )
    (net (code "63") (name "Net-(R79-Pad1)") (class "Default")
      (node (ref "R79") (pin "1") (pinfunction "1_1") (pintype "passive"))
      (node (ref "X16") (pin "9") (pinfunction "9_9") (pintype "passive"))
    )
    (net (code "64") (name "Net-(R81-Pad1)") (class "Default")
      (node (ref "R81") (pin "1") (pinfunction "1_1") (pintype "passive"))
      (node (ref "X16") (pin "1") (pinfunction "1_1") (pintype "passive"))
    )
    (net (code "65") (name "Net-(R82-Pad1)") (class "Default")
      (node (ref "R82") (pin "1") (pinfunction "1_1") (pintype "passive"))
      (node (ref "X16") (pin "2") (pinfunction "2_2") (pintype "passive"))
    )
    (net (code "66") (name "Net-(R83-Pad1)") (class "Default")
      (node (ref "R83") (pin "1") (pinfunction "1_1") (pintype "passive"))
      (node (ref "X16") (pin "3") (pinfunction "3_3") (pintype "passive"))
    )
    (net (code "67") (name "Net-(R84-Pad1)") (class "Default")
      (node (ref "R84") (pin "1") (pinfunction "1_1") (pintype "passive"))
      (node (ref "X16") (pin "4") (pinfunction "4_4") (pintype "passive"))
    )
    (net (code "68") (name "Net-(R85-Pad1)") (class "Default")
      (node (ref "R85") (pin "1") (pinfunction "1_1") (pintype "passive"))
      (node (ref "X16") (pin "5") (pinfunction "5_5") (pintype "passive"))
    )
    (net (code "69") (name "Net-(R86-Pad1)") (class "Default")
      (node (ref "R86") (pin "1") (pinfunction "1_1") (pintype "passive"))
      (node (ref "X16") (pin "6") (pinfunction "6_6") (pintype "passive"))
    )
    (net (code "70") (name "Net-(R87-Pad1)") (class "Default")
      (node (ref "R87") (pin "1") (pinfunction "1_1") (pintype "passive"))
      (node (ref "X16") (pin "7") (pinfunction "7_7") (pintype "passive"))
    )
    (net (code "71") (name "Net-(R88-Pad1)") (class "Default")
      (node (ref "R88") (pin "1") (pinfunction "1_1") (pintype "passive"))
      (node (ref "X16") (pin "8") (pinfunction "8_8") (pintype "passive"))
    )
    (net (code "72") (name "Net-(U6-SO)") (class "Default")
      (node (ref "R149") (pin "2") (pinfunction "2_2") (pintype "passive"))
      (node (ref "U6") (pin "2") (pinfunction "SO_2") (pintype "passive"))
      (node (ref "U6A") (pin "8") (pinfunction "SO_8") (pintype "passive"))
    )
    (net (code "73") (name "Net-(U8E-RFUSE)") (class "Default")
      (node (ref "R24") (pin "2") (pinfunction "2_2") (pintype "passive"))
      (node (ref "R67") (pin "2") (pinfunction "2_2") (pintype "passive"))
      (node (ref "U8") (pin "P15") (pinfunction "RFUSE_P15") (pintype "input"))
    )
    (net (code "74") (name "Net-(U8E-SUSPEND)") (class "Default")
      (node (ref "R23") (pin "2") (pinfunction "2_2") (pintype "passive"))
      (node (ref "U8") (pin "N15") (pinfunction "SUSPEND_N15") (pintype "input"))
    )
    (net (code "75") (name "Net-(U8E-TCK)") (class "Default")
      (node (ref "R15") (pin "2") (pinfunction "2_2") (pintype "passive"))
      (node (ref "R20") (pin "1") (pinfunction "1_1") (pintype "passive"))
      (node (ref "U8") (pin "G15") (pinfunction "TCK_G15") (pintype "input"))
    )
    (net (code "76") (name "Net-(U8E-TDI)") (class "Default")
      (node (ref "R17") (pin "2") (pinfunction "2_2") (pintype "passive"))
      (node (ref "R19") (pin "2") (pinfunction "2_2") (pintype "passive"))
      (node (ref "U8") (pin "E18") (pinfunction "TDI_E18") (pintype "input"))
    )
    (net (code "77") (name "Net-(U8E-TDO)") (class "Default")
      (node (ref "R16") (pin "2") (pinfunction "2_2") (pintype "passive"))
      (node (ref "U8") (pin "A19") (pinfunction "TDO_A19") (pintype "output"))
    )
    (net (code "78") (name "Net-(U8E-TMS)") (class "Default")
      (node (ref "R14") (pin "2") (pinfunction "2_2") (pintype "passive"))
      (node (ref "R18") (pin "2") (pinfunction "2_2") (pintype "passive"))
      (node (ref "U8") (pin "C18") (pinfunction "TMS_C18") (pintype "input"))
    )
    (net (code "79") (name "Net-(U8E-VFS)") (class "Default")
      (node (ref "R21") (pin "2") (pinfunction "2_2") (pintype "passive"))
      (node (ref "U8") (pin "P16") (pinfunction "VFS_P16") (pintype "input"))
    )
    (net (code "80") (name "Net-(U33-3V3OUT)") (class "Default")
      (node (ref "C300") (pin "2") (pinfunction "2_2") (pintype "passive"))
      (node (ref "U33") (pin "17") (pinfunction "3V3OUT_17") (pintype "power_in"))
      (node (ref "U33") (pin "4") (pinfunction "VCCIO_4") (pintype "power_in"))
    )
    (net (code "81") (name "Net-(U33-RXD)") (class "Default")
      (node (ref "R164") (pin "2") (pinfunction "2_2") (pintype "passive"))
      (node (ref "U33") (pin "5") (pinfunction "RXD_5") (pintype "input"))
    )
    (net (code "82") (name "Net-(U33-TXD)") (class "Default")
      (node (ref "R163") (pin "2") (pinfunction "2_2") (pintype "passive"))
      (node (ref "U33") (pin "1") (pinfunction "TXD_1") (pintype "output"))
    )
    (net (code "83") (name "Net-(U33-USBDM)") (class "Default")
      (node (ref "U33") (pin "16") (pinfunction "USBDM_16") (pintype "bidirectional"))
      (node (ref "X3") (pin "2") (pinfunction "D_2") (pintype "bidirectional"))
    )
    (net (code "84") (name "Net-(U33-USBDP)") (class "Default")
      (node (ref "U33") (pin "15") (pinfunction "USBDP_15") (pintype "bidirectional"))
      (node (ref "X3") (pin "3") (pinfunction "D+_3") (pintype "bidirectional"))
    )
    (net (code "85") (name "Net-(U33-~{CTS})") (class "Default")
      (node (ref "R166") (pin "2") (pinfunction "2_2") (pintype "passive"))
      (node (ref "U33") (pin "11") (pinfunction "~{CTS}_11") (pintype "input"))
    )
    (net (code "86") (name "Net-(U33-~{DSR})") (class "Default")
      (node (ref "R165") (pin "2") (pinfunction "2_2") (pintype "passive"))
      (node (ref "U33") (pin "9") (pinfunction "~{DSR}_9") (pintype "input"))
    )
    (net (code "87") (name "Net-(U33-~{DTR})") (class "Default")
      (node (ref "R165") (pin "1") (pinfunction "1_1") (pintype "passive"))
      (node (ref "U33") (pin "2") (pinfunction "~{DTR}_2") (pintype "output"))
    )
    (net (code "88") (name "Net-(U33-~{RTS})") (class "Default")
      (node (ref "R166") (pin "1") (pinfunction "1_1") (pintype "passive"))
      (node (ref "U33") (pin "3") (pinfunction "~{RTS}_3") (pintype "output"))
    )
    (net (code "89") (name "Net-(X3-V_BUS)") (class "Default")
      (node (ref "C297") (pin "2") (pinfunction "2_2") (pintype "passive"))
      (node (ref "L46") (pin "1") (pinfunction "1_1") (pintype "passive"))
      (node (ref "X3") (pin "1") (pinfunction "V_BUS_1") (pintype "power_in"))
    )
    (net (code "90") (name "unconnected-(U8C-IO_L2N_CMPMOSI_2-PadAB21)") (class "Default")
      (node (ref "U8") (pin "AB21") (pinfunction "IO_L2N_CMPMOSI_2_AB21") (pintype "bidirectional+no_connect"))
    )
    (net (code "91") (name "unconnected-(U8C-IO_L2P_CMPCLK_2-PadAA21)") (class "Default")
      (node (ref "U8") (pin "AA21") (pinfunction "IO_L2P_CMPCLK_2_AA21") (pintype "bidirectional+no_connect"))
    )
    (net (code "92") (name "unconnected-(U8C-IO_L12N_D2_MISO3_2-PadU13)") (class "Default")
      (node (ref "U8") (pin "U13") (pinfunction "IO_L12N_D2_MISO3_2_U13") (pintype "bidirectional+no_connect"))
    )
    (net (code "93") (name "unconnected-(U8C-IO_L12P_D1_MISO2_2-PadU14)") (class "Default")
      (node (ref "U8") (pin "U14") (pinfunction "IO_L12P_D1_MISO2_2_U14") (pintype "bidirectional+no_connect"))
    )
    (net (code "94") (name "unconnected-(U8C-IO_L13N_D10_2-PadV15)") (class "Default")
      (node (ref "U8") (pin "V15") (pinfunction "IO_L13N_D10_2_V15") (pintype "bidirectional+no_connect"))
    )
    (net (code "95") (name "unconnected-(U8C-IO_L19N_2-PadAB16)") (class "Default")
      (node (ref "U8") (pin "AB16") (pinfunction "IO_L19N_2_AB16") (pintype "bidirectional+no_connect"))
    )
    (net (code "96") (name "unconnected-(U8C-IO_L21N_2-PadAB15)") (class "Default")
      (node (ref "U8") (pin "AB15") (pinfunction "IO_L21N_2_AB15") (pintype "bidirectional+no_connect"))
    )
    (net (code "97") (name "unconnected-(U8C-IO_L29N_GCLK2_2-PadY12)") (class "Default")
      (node (ref "U8") (pin "Y12") (pinfunction "IO_L29N_GCLK2_2_Y12") (pintype "bidirectional+no_connect"))
    )
    (net (code "98") (name "unconnected-(U8C-IO_L30P_GCLK1_D13_2-PadY13)") (class "Default")
      (node (ref "U8") (pin "Y13") (pinfunction "IO_L30P_GCLK1_D13_2_Y13") (pintype "bidirectional+no_connect"))
    )
    (net (code "99") (name "unconnected-(U8C-IO_L31P_GCLK31_D14_2-PadAA12)") (class "Default")
      (node (ref "U8") (pin "AA12") (pinfunction "IO_L31P_GCLK31_D14_2_AA12") (pintype "bidirectional+no_connect"))
    )
    (net (code "100") (name "unconnected-(U8C-IO_L32P_GCLK29_2-PadY11)") (class "Default")
      (node (ref "U8") (pin "Y11") (pinfunction "IO_L32P_GCLK29_2_Y11") (pintype "bidirectional+no_connect"))
    )
    (net (code "101") (name "unconnected-(U8C-IO_L41P_2-PadAA10)") (class "Default")
      (node (ref "U8") (pin "AA10") (pinfunction "IO_L41P_2_AA10") (pintype "bidirectional+no_connect"))
    )
    (net (code "102") (name "unconnected-(U8C-IO_L42N_2-PadW11)") (class "Default")
      (node (ref "U8") (pin "W11") (pinfunction "IO_L42N_2_W11") (pintype "bidirectional+no_connect"))
    )
    (net (code "103") (name "unconnected-(U8C-IO_L42P_2-PadV11)") (class "Default")
      (node (ref "U8") (pin "V11") (pinfunction "IO_L42P_2_V11") (pintype "bidirectional+no_connect"))
    )
    (net (code "104") (name "unconnected-(U8C-IO_L43P_2-PadY9)") (class "Default")
      (node (ref "U8") (pin "Y9") (pinfunction "IO_L43P_2_Y9") (pintype "bidirectional+no_connect"))
    )
    (net (code "105") (name "unconnected-(U8C-IO_L48P_D7_2-PadY7)") (class "Default")
      (node (ref "U8") (pin "Y7") (pinfunction "IO_L48P_D7_2_Y7") (pintype "bidirectional+no_connect"))
    )
    (net (code "106") (name "unconnected-(U8E-CMPCS_B_2-PadY20)") (class "Default")
      (node (ref "U8") (pin "Y20") (pinfunction "CMPCS_B_2_Y20") (pintype "input+no_connect"))
    )
    (net (code "107") (name "unconnected-(U33-CBUS0-Pad23)") (class "Default")
      (node (ref "U33") (pin "23") (pinfunction "CBUS0_23") (pintype "bidirectional+no_connect"))
    )
    (net (code "108") (name "unconnected-(U33-CBUS1-Pad22)") (class "Default")
      (node (ref "U33") (pin "22") (pinfunction "CBUS1_22") (pintype "bidirectional+no_connect"))
    )
    (net (code "109") (name "unconnected-(U33-CBUS2-Pad13)") (class "Default")
      (node (ref "U33") (pin "13") (pinfunction "CBUS2_13") (pintype "bidirectional+no_connect"))
    )
    (net (code "110") (name "unconnected-(U33-CBUS3-Pad14)") (class "Default")
      (node (ref "U33") (pin "14") (pinfunction "CBUS3_14") (pintype "bidirectional+no_connect"))
    )
    (net (code "111") (name "unconnected-(U33-CBUS4-Pad12)") (class "Default")
      (node (ref "U33") (pin "12") (pinfunction "CBUS4_12") (pintype "bidirectional+no_connect"))
    )
    (net (code "112") (name "unconnected-(U33-NC-Pad8)") (class "Default")
      (node (ref "U33") (pin "8") (pinfunction "NC_8") (pintype "passive+no_connect"))
    )
    (net (code "113") (name "unconnected-(U33-NC-Pad24)") (class "Default")
      (node (ref "U33") (pin "24") (pinfunction "NC_24") (pintype "passive+no_connect"))
    )
    (net (code "114") (name "unconnected-(U33-OSCI-Pad27)") (class "Default")
      (node (ref "U33") (pin "27") (pinfunction "OSCI_27") (pintype "input+no_connect"))
    )
    (net (code "115") (name "unconnected-(U33-OSCO-Pad28)") (class "Default")
      (node (ref "U33") (pin "28") (pinfunction "OSCO_28") (pintype "output+no_connect"))
    )
    (net (code "116") (name "unconnected-(U33-~{DCD}-Pad10)") (class "Default")
      (node (ref "U33") (pin "10") (pinfunction "~{DCD}_10") (pintype "input+no_connect"))
    )
    (net (code "117") (name "unconnected-(U33-~{RESET}-Pad19)") (class "Default")
      (node (ref "U33") (pin "19") (pinfunction "~{RESET}_19") (pintype "input+no_connect"))
    )
    (net (code "118") (name "unconnected-(U33-~{RI}-Pad6)") (class "Default")
      (node (ref "U33") (pin "6") (pinfunction "~{RI}_6") (pintype "input+no_connect"))
    )
    (net (code "119") (name "unconnected-(X1-Pad12)") (class "Default")
      (node (ref "X1") (pin "12") (pinfunction "12_12") (pintype "passive+no_connect"))
    )
    (net (code "120") (name "unconnected-(X1-Pad14)") (class "Default")
      (node (ref "X1") (pin "14") (pinfunction "14_14") (pintype "passive+no_connect"))
    )
  )
)
